# jarvis-2_0.net
KiCad netlist of a schematic drawn in EAGLE
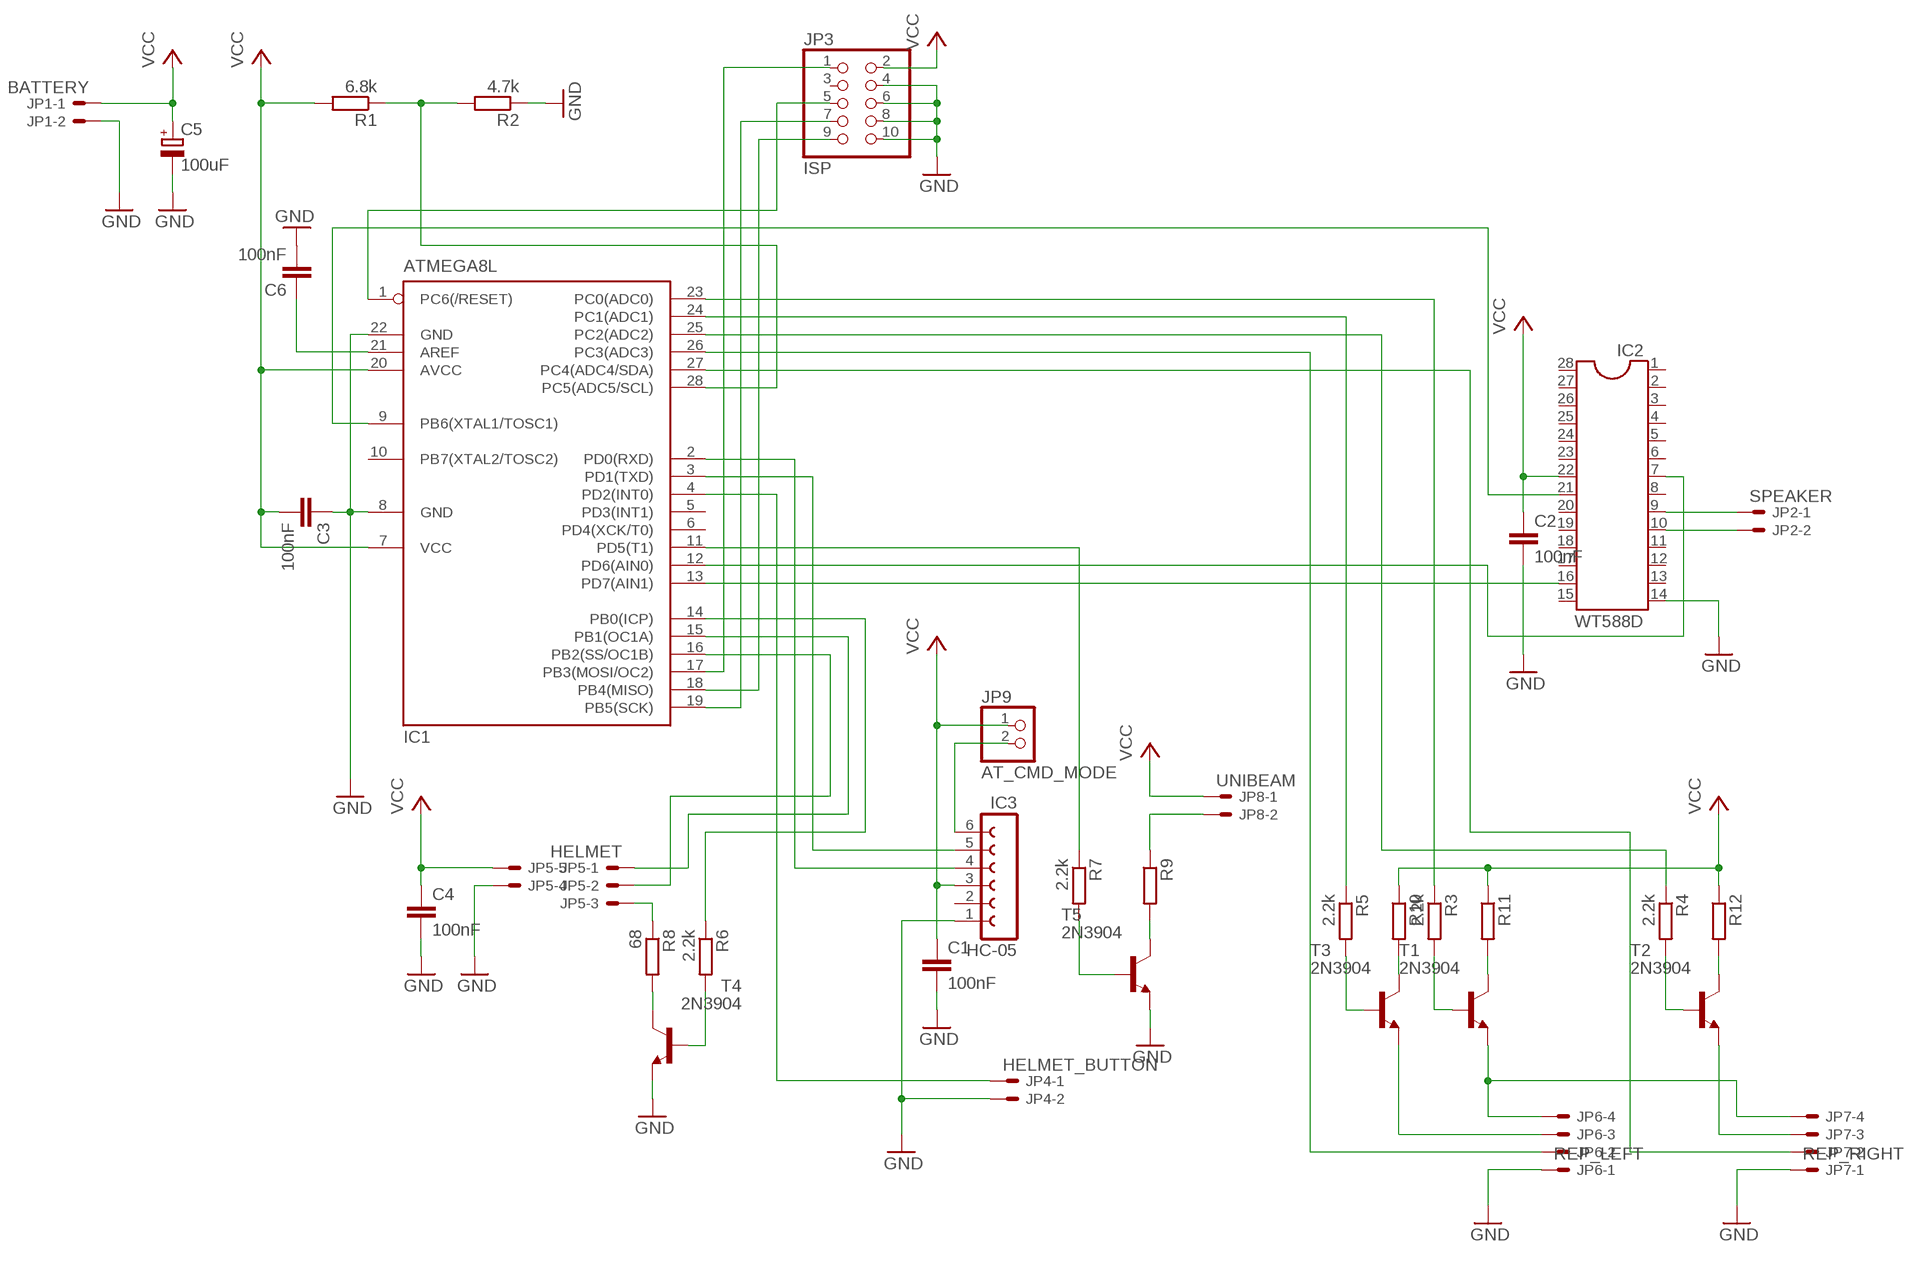
[diagram p0: schematic, sheet 1]

(export (version "E")
  (design (tool "Eeschema 10.0.6"))
  (components
    (comp (ref "C1")
      (value "100nF")
      (footprint "eagle-import:C2.5-2")
      (libsource (lib "eagle-import") (part "C2.5/2"))
    )
    (comp (ref "C2")
      (value "100nF")
      (footprint "eagle-import:C2.5-2")
      (libsource (lib "eagle-import") (part "C2.5/2"))
    )
    (comp (ref "C3")
      (value "100nF")
      (footprint "eagle-import:C2.5-2")
      (libsource (lib "eagle-import") (part "C2.5/2"))
    )
    (comp (ref "C4")
      (value "100nF")
      (footprint "eagle-import:C2.5-2")
      (libsource (lib "eagle-import") (part "C2.5/2"))
    )
    (comp (ref "C5")
      (value "100uF")
      (footprint "eagle-import:E5-5")
      (libsource (lib "eagle-import") (part "CPOL-EUE5-5"))
    )
    (comp (ref "C6")
      (value "100nF")
      (footprint "eagle-import:C2.5-2")
      (libsource (lib "eagle-import") (part "C2.5/2"))
    )
    (comp (ref "IC1")
      (value "ATMEGA8L")
      (footprint "eagle-import:DIL28-3")
      (libsource (lib "eagle-import") (part "MEGA8-P"))
    )
    (comp (ref "IC2")
      (value "WT588D")
      (footprint "eagle-import:DIL28-6")
      (libsource (lib "eagle-import") (part "DIL28"))
    )
    (comp (ref "IC3")
      (value "HC-05")
      (footprint "eagle-import:FE06")
      (libsource (lib "eagle-import") (part "FE06-1"))
    )
    (comp (ref "JP1")
      (value "BATTERY")
      (footprint "eagle-import:22-23-2021")
      (fields (field (name "MF") "MOLEX") (field (name "MPN") "22-23-2021"))
      (libsource (lib "eagle-import") (part "22-23-2021"))
    )
    (comp (ref "JP2")
      (value "SPEAKER")
      (footprint "eagle-import:22-23-2021")
      (fields (field (name "MF") "MOLEX") (field (name "MPN") "22-23-2021"))
      (libsource (lib "eagle-import") (part "22-23-2021"))
    )
    (comp (ref "JP3")
      (value "ISP")
      (footprint "eagle-import:2X05")
      (libsource (lib "eagle-import") (part "PINHD-2X5"))
    )
    (comp (ref "JP4")
      (value "HELMET_BUTTON")
      (footprint "eagle-import:22-23-2021")
      (fields (field (name "MF") "MOLEX") (field (name "MPN") "22-23-2021"))
      (libsource (lib "eagle-import") (part "22-23-2021"))
    )
    (comp (ref "JP5")
      (value "HELMET")
      (footprint "eagle-import:22-23-2051")
      (fields (field (name "MF") "MOLEX") (field (name "MPN") "22-23-2051"))
      (libsource (lib "eagle-import") (part "22-23-2051"))
    )
    (comp (ref "JP6")
      (value "REP_LEFT")
      (footprint "eagle-import:22-23-2041")
      (fields (field (name "MF") "MOLEX") (field (name "MPN") "22-23-2041"))
      (libsource (lib "eagle-import") (part "22-23-2041"))
    )
    (comp (ref "JP7")
      (value "REP_RIGHT")
      (footprint "eagle-import:22-23-2041")
      (fields (field (name "MF") "MOLEX") (field (name "MPN") "22-23-2041"))
      (libsource (lib "eagle-import") (part "22-23-2041"))
    )
    (comp (ref "JP8")
      (value "UNIBEAM")
      (footprint "eagle-import:22-23-2021")
      (fields (field (name "MF") "MOLEX") (field (name "MPN") "22-23-2021"))
      (libsource (lib "eagle-import") (part "22-23-2021"))
    )
    (comp (ref "JP9")
      (value "AT_CMD_MODE")
      (footprint "eagle-import:1X02")
      (libsource (lib "eagle-import") (part "PINHD-1X2"))
    )
    (comp (ref "R1")
      (value "6.8k")
      (footprint "eagle-import:0204_7")
      (libsource (lib "eagle-import") (part "R-EU_0204/7"))
    )
    (comp (ref "R2")
      (value "4.7k")
      (footprint "eagle-import:0204_7")
      (libsource (lib "eagle-import") (part "R-EU_0204/7"))
    )
    (comp (ref "R3")
      (value "2.2k")
      (footprint "eagle-import:0204_7")
      (libsource (lib "eagle-import") (part "R-EU_0204/7"))
    )
    (comp (ref "R4")
      (value "2.2k")
      (footprint "eagle-import:0204_7")
      (libsource (lib "eagle-import") (part "R-EU_0204/7"))
    )
    (comp (ref "R5")
      (value "2.2k")
      (footprint "eagle-import:0204_7")
      (libsource (lib "eagle-import") (part "R-EU_0204/7"))
    )
    (comp (ref "R6")
      (value "2.2k")
      (footprint "eagle-import:0204_7")
      (libsource (lib "eagle-import") (part "R-EU_0204/7"))
    )
    (comp (ref "R7")
      (value "2.2k")
      (footprint "eagle-import:0204_7")
      (libsource (lib "eagle-import") (part "R-EU_0204/7"))
    )
    (comp (ref "R8")
      (value "68")
      (footprint "eagle-import:0204_7")
      (libsource (lib "eagle-import") (part "R-EU_0204/7"))
    )
    (comp (ref "R9")
      (value "R-EU_0204/7")
      (footprint "eagle-import:0204_7")
      (libsource (lib "eagle-import") (part "R-EU_0204/7"))
    )
    (comp (ref "R10")
      (value "R-EU_0204/7")
      (footprint "eagle-import:0204_7")
      (libsource (lib "eagle-import") (part "R-EU_0204/7"))
    )
    (comp (ref "R11")
      (value "R-EU_0204/7")
      (footprint "eagle-import:0204_7")
      (libsource (lib "eagle-import") (part "R-EU_0204/7"))
    )
    (comp (ref "R12")
      (value "R-EU_0204/7")
      (footprint "eagle-import:0204_7")
      (libsource (lib "eagle-import") (part "R-EU_0204/7"))
    )
    (comp (ref "T1")
      (value "2N3904")
      (footprint "eagle-import:TO92-CBE")
      (libsource (lib "eagle-import") (part "-NPN-TO92-CBEBC546"))
    )
    (comp (ref "T2")
      (value "2N3904")
      (footprint "eagle-import:TO92-CBE")
      (libsource (lib "eagle-import") (part "-NPN-TO92-CBEBC546"))
    )
    (comp (ref "T3")
      (value "2N3904")
      (footprint "eagle-import:TO92-CBE")
      (libsource (lib "eagle-import") (part "-NPN-TO92-CBEBC546"))
    )
    (comp (ref "T4")
      (value "2N3904")
      (footprint "eagle-import:TO92-CBE")
      (libsource (lib "eagle-import") (part "-NPN-TO92-CBEBC546"))
    )
    (comp (ref "T5")
      (value "2N3904")
      (footprint "eagle-import:TO92-CBE")
      (libsource (lib "eagle-import") (part "-NPN-TO92-CBEBC546"))
    )
  )
  (nets
    (net (code "1") (name "GND") (class "Default")
      (node (ref "C1") (pin "2") (pinfunction "2_2") (pintype "passive"))
      (node (ref "C2") (pin "2") (pinfunction "2_2") (pintype "passive"))
      (node (ref "C3") (pin "1") (pinfunction "1_1") (pintype "passive"))
      (node (ref "C4") (pin "2") (pinfunction "2_2") (pintype "passive"))
      (node (ref "C5") (pin "-") (pinfunction "-_-") (pintype "passive"))
      (node (ref "C6") (pin "2") (pinfunction "2_2") (pintype "passive"))
      (node (ref "IC1") (pin "22") (pinfunction "GND_22") (pintype "power_in"))
      (node (ref "IC1") (pin "8") (pinfunction "GND_8") (pintype "power_in"))
      (node (ref "IC2") (pin "14") (pinfunction "14_14") (pintype "passive"))
      (node (ref "IC3") (pin "1") (pinfunction "1_1") (pintype "passive"))
      (node (ref "JP1") (pin "2") (pinfunction "S_2") (pintype "passive"))
      (node (ref "JP3") (pin "10") (pinfunction "10_10") (pintype "passive"))
      (node (ref "JP3") (pin "4") (pinfunction "4_4") (pintype "passive"))
      (node (ref "JP3") (pin "6") (pinfunction "6_6") (pintype "passive"))
      (node (ref "JP3") (pin "8") (pinfunction "8_8") (pintype "passive"))
      (node (ref "JP4") (pin "2") (pinfunction "S_2") (pintype "passive"))
      (node (ref "JP5") (pin "4") (pinfunction "S_4") (pintype "passive"))
      (node (ref "JP6") (pin "1") (pinfunction "S_1") (pintype "passive"))
      (node (ref "JP7") (pin "1") (pinfunction "S_1") (pintype "passive"))
      (node (ref "R2") (pin "1") (pinfunction "1_1") (pintype "passive"))
      (node (ref "T4") (pin "E") (pinfunction "E_E") (pintype "passive"))
      (node (ref "T5") (pin "E") (pinfunction "E_E") (pintype "passive"))
    )
    (net (code "2") (name "Net-(IC1-AREF)") (class "Default")
      (node (ref "C6") (pin "1") (pinfunction "1_1") (pintype "passive"))
      (node (ref "IC1") (pin "21") (pinfunction "AREF_21") (pintype "passive"))
    )
    (net (code "3") (name "Net-(IC1-PB0(ICP))") (class "Default")
      (node (ref "IC1") (pin "14") (pinfunction "PB0(ICP)_14") (pintype "bidirectional"))
      (node (ref "R6") (pin "1") (pinfunction "1_1") (pintype "passive"))
    )
    (net (code "4") (name "Net-(IC1-PB1(OC1A))") (class "Default")
      (node (ref "IC1") (pin "15") (pinfunction "PB1(OC1A)_15") (pintype "bidirectional"))
      (node (ref "JP5") (pin "1") (pinfunction "S_1") (pintype "passive"))
    )
    (net (code "5") (name "Net-(IC1-PB2(SS{slash}OC1B))") (class "Default")
      (node (ref "IC1") (pin "16") (pinfunction "PB2(SS/OC1B)_16") (pintype "bidirectional"))
      (node (ref "JP5") (pin "2") (pinfunction "S_2") (pintype "passive"))
    )
    (net (code "6") (name "Net-(IC1-PB3(MOSI{slash}OC2))") (class "Default")
      (node (ref "IC1") (pin "17") (pinfunction "PB3(MOSI/OC2)_17") (pintype "bidirectional"))
      (node (ref "JP3") (pin "1") (pinfunction "1_1") (pintype "passive"))
    )
    (net (code "7") (name "Net-(IC1-PB4(MISO))") (class "Default")
      (node (ref "IC1") (pin "18") (pinfunction "PB4(MISO)_18") (pintype "bidirectional"))
      (node (ref "JP3") (pin "9") (pinfunction "9_9") (pintype "passive"))
    )
    (net (code "8") (name "Net-(IC1-PB5(SCK))") (class "Default")
      (node (ref "IC1") (pin "19") (pinfunction "PB5(SCK)_19") (pintype "bidirectional"))
      (node (ref "JP3") (pin "7") (pinfunction "7_7") (pintype "passive"))
    )
    (net (code "9") (name "Net-(IC1-PB6(XTAL1{slash}TOSC1))") (class "Default")
      (node (ref "IC1") (pin "9") (pinfunction "PB6(XTAL1/TOSC1)_9") (pintype "bidirectional"))
      (node (ref "IC2") (pin "21") (pinfunction "21_21") (pintype "passive"))
    )
    (net (code "10") (name "Net-(IC1-PC0(ADC0))") (class "Default")
      (node (ref "IC1") (pin "23") (pinfunction "PC0(ADC0)_23") (pintype "bidirectional"))
      (node (ref "R3") (pin "1") (pinfunction "1_1") (pintype "passive"))
    )
    (net (code "11") (name "Net-(IC1-PC1(ADC1))") (class "Default")
      (node (ref "IC1") (pin "24") (pinfunction "PC1(ADC1)_24") (pintype "bidirectional"))
      (node (ref "R5") (pin "1") (pinfunction "1_1") (pintype "passive"))
    )
    (net (code "12") (name "Net-(IC1-PC2(ADC2))") (class "Default")
      (node (ref "IC1") (pin "25") (pinfunction "PC2(ADC2)_25") (pintype "bidirectional"))
      (node (ref "R4") (pin "1") (pinfunction "1_1") (pintype "passive"))
    )
    (net (code "13") (name "Net-(IC1-PC3(ADC3))") (class "Default")
      (node (ref "IC1") (pin "26") (pinfunction "PC3(ADC3)_26") (pintype "bidirectional"))
      (node (ref "JP6") (pin "2") (pinfunction "S_2") (pintype "passive"))
    )
    (net (code "14") (name "Net-(IC1-PC4(ADC4{slash}SDA))") (class "Default")
      (node (ref "IC1") (pin "27") (pinfunction "PC4(ADC4/SDA)_27") (pintype "bidirectional"))
      (node (ref "JP7") (pin "2") (pinfunction "S_2") (pintype "passive"))
    )
    (net (code "15") (name "Net-(IC1-PC5(ADC5{slash}SCL))") (class "Default")
      (node (ref "IC1") (pin "28") (pinfunction "PC5(ADC5/SCL)_28") (pintype "bidirectional"))
      (node (ref "R1") (pin "1") (pinfunction "1_1") (pintype "passive"))
      (node (ref "R2") (pin "2") (pinfunction "2_2") (pintype "passive"))
    )
    (net (code "16") (name "Net-(IC1-PC6({slash}RESET))") (class "Default")
      (node (ref "IC1") (pin "1") (pinfunction "PC6(/RESET)_1") (pintype "bidirectional"))
      (node (ref "JP3") (pin "5") (pinfunction "5_5") (pintype "passive"))
    )
    (net (code "17") (name "Net-(IC1-PD0(RXD))") (class "Default")
      (node (ref "IC1") (pin "2") (pinfunction "PD0(RXD)_2") (pintype "bidirectional"))
      (node (ref "IC3") (pin "4") (pinfunction "4_4") (pintype "passive"))
    )
    (net (code "18") (name "Net-(IC1-PD1(TXD))") (class "Default")
      (node (ref "IC1") (pin "3") (pinfunction "PD1(TXD)_3") (pintype "bidirectional"))
      (node (ref "IC3") (pin "5") (pinfunction "5_5") (pintype "passive"))
    )
    (net (code "19") (name "Net-(IC1-PD2(INT0))") (class "Default")
      (node (ref "IC1") (pin "4") (pinfunction "PD2(INT0)_4") (pintype "bidirectional"))
      (node (ref "JP4") (pin "1") (pinfunction "S_1") (pintype "passive"))
    )
    (net (code "20") (name "Net-(IC1-PD5(T1))") (class "Default")
      (node (ref "IC1") (pin "11") (pinfunction "PD5(T1)_11") (pintype "bidirectional"))
      (node (ref "R7") (pin "1") (pinfunction "1_1") (pintype "passive"))
    )
    (net (code "21") (name "Net-(IC1-PD6(AIN0))") (class "Default")
      (node (ref "IC1") (pin "12") (pinfunction "PD6(AIN0)_12") (pintype "bidirectional"))
      (node (ref "IC2") (pin "7") (pinfunction "7_7") (pintype "passive"))
    )
    (net (code "22") (name "Net-(IC1-PD7(AIN1))") (class "Default")
      (node (ref "IC1") (pin "13") (pinfunction "PD7(AIN1)_13") (pintype "bidirectional"))
      (node (ref "IC2") (pin "16") (pinfunction "16_16") (pintype "passive"))
    )
    (net (code "23") (name "Net-(IC3-Pad6)") (class "Default")
      (node (ref "IC3") (pin "6") (pinfunction "6_6") (pintype "passive"))
      (node (ref "JP9") (pin "2") (pinfunction "2_2") (pintype "passive"))
    )
    (net (code "24") (name "Net-(JP2A-S)") (class "Default")
      (node (ref "IC2") (pin "9") (pinfunction "9_9") (pintype "passive"))
      (node (ref "JP2") (pin "1") (pinfunction "S_1") (pintype "passive"))
    )
    (net (code "25") (name "Net-(JP2B-S)") (class "Default")
      (node (ref "IC2") (pin "10") (pinfunction "10_10") (pintype "passive"))
      (node (ref "JP2") (pin "2") (pinfunction "S_2") (pintype "passive"))
    )
    (net (code "26") (name "Net-(JP5C-S)") (class "Default")
      (node (ref "JP5") (pin "3") (pinfunction "S_3") (pintype "passive"))
      (node (ref "R8") (pin "1") (pinfunction "1_1") (pintype "passive"))
    )
    (net (code "27") (name "Net-(JP6C-S)") (class "Default")
      (node (ref "JP6") (pin "3") (pinfunction "S_3") (pintype "passive"))
      (node (ref "T3") (pin "E") (pinfunction "E_E") (pintype "passive"))
    )
    (net (code "28") (name "Net-(JP6D-S)") (class "Default")
      (node (ref "JP6") (pin "4") (pinfunction "S_4") (pintype "passive"))
      (node (ref "JP7") (pin "4") (pinfunction "S_4") (pintype "passive"))
      (node (ref "T1") (pin "E") (pinfunction "E_E") (pintype "passive"))
    )
    (net (code "29") (name "Net-(JP7C-S)") (class "Default")
      (node (ref "JP7") (pin "3") (pinfunction "S_3") (pintype "passive"))
      (node (ref "T2") (pin "E") (pinfunction "E_E") (pintype "passive"))
    )
    (net (code "30") (name "Net-(JP8B-S)") (class "Default")
      (node (ref "JP8") (pin "2") (pinfunction "S_2") (pintype "passive"))
      (node (ref "R9") (pin "1") (pinfunction "1_1") (pintype "passive"))
    )
    (net (code "31") (name "Net-(R3-Pad2)") (class "Default")
      (node (ref "R3") (pin "2") (pinfunction "2_2") (pintype "passive"))
      (node (ref "T1") (pin "B") (pinfunction "B_B") (pintype "passive"))
    )
    (net (code "32") (name "Net-(R4-Pad2)") (class "Default")
      (node (ref "R4") (pin "2") (pinfunction "2_2") (pintype "passive"))
      (node (ref "T2") (pin "B") (pinfunction "B_B") (pintype "passive"))
    )
    (net (code "33") (name "Net-(R5-Pad2)") (class "Default")
      (node (ref "R5") (pin "2") (pinfunction "2_2") (pintype "passive"))
      (node (ref "T3") (pin "B") (pinfunction "B_B") (pintype "passive"))
    )
    (net (code "34") (name "Net-(R6-Pad2)") (class "Default")
      (node (ref "R6") (pin "2") (pinfunction "2_2") (pintype "passive"))
      (node (ref "T4") (pin "B") (pinfunction "B_B") (pintype "passive"))
    )
    (net (code "35") (name "Net-(R7-Pad2)") (class "Default")
      (node (ref "R7") (pin "2") (pinfunction "2_2") (pintype "passive"))
      (node (ref "T5") (pin "B") (pinfunction "B_B") (pintype "passive"))
    )
    (net (code "36") (name "Net-(R8-Pad2)") (class "Default")
      (node (ref "R8") (pin "2") (pinfunction "2_2") (pintype "passive"))
      (node (ref "T4") (pin "C") (pinfunction "C_C") (pintype "passive"))
    )
    (net (code "37") (name "Net-(R9-Pad2)") (class "Default")
      (node (ref "R9") (pin "2") (pinfunction "2_2") (pintype "passive"))
      (node (ref "T5") (pin "C") (pinfunction "C_C") (pintype "passive"))
    )
    (net (code "38") (name "Net-(R10-Pad2)") (class "Default")
      (node (ref "R10") (pin "2") (pinfunction "2_2") (pintype "passive"))
      (node (ref "T3") (pin "C") (pinfunction "C_C") (pintype "passive"))
    )
    (net (code "39") (name "Net-(R11-Pad2)") (class "Default")
      (node (ref "R11") (pin "2") (pinfunction "2_2") (pintype "passive"))
      (node (ref "T1") (pin "C") (pinfunction "C_C") (pintype "passive"))
    )
    (net (code "40") (name "Net-(R12-Pad2)") (class "Default")
      (node (ref "R12") (pin "2") (pinfunction "2_2") (pintype "passive"))
      (node (ref "T2") (pin "C") (pinfunction "C_C") (pintype "passive"))
    )
    (net (code "41") (name "VCC") (class "Default")
      (node (ref "C1") (pin "1") (pinfunction "1_1") (pintype "passive"))
      (node (ref "C2") (pin "1") (pinfunction "1_1") (pintype "passive"))
      (node (ref "C3") (pin "2") (pinfunction "2_2") (pintype "passive"))
      (node (ref "C4") (pin "1") (pinfunction "1_1") (pintype "passive"))
      (node (ref "C5") (pin "+") (pinfunction "+_+") (pintype "passive"))
      (node (ref "IC1") (pin "20") (pinfunction "AVCC_20") (pintype "power_in"))
      (node (ref "IC1") (pin "7") (pinfunction "VCC_7") (pintype "power_in"))
      (node (ref "IC2") (pin "22") (pinfunction "22_22") (pintype "passive"))
      (node (ref "IC3") (pin "3") (pinfunction "3_3") (pintype "passive"))
      (node (ref "JP1") (pin "1") (pinfunction "S_1") (pintype "passive"))
      (node (ref "JP3") (pin "2") (pinfunction "2_2") (pintype "passive"))
      (node (ref "JP5") (pin "5") (pinfunction "S_5") (pintype "passive"))
      (node (ref "JP8") (pin "1") (pinfunction "S_1") (pintype "passive"))
      (node (ref "JP9") (pin "1") (pinfunction "1_1") (pintype "passive"))
      (node (ref "R1") (pin "2") (pinfunction "2_2") (pintype "passive"))
      (node (ref "R10") (pin "1") (pinfunction "1_1") (pintype "passive"))
      (node (ref "R11") (pin "1") (pinfunction "1_1") (pintype "passive"))
      (node (ref "R12") (pin "1") (pinfunction "1_1") (pintype "passive"))
    )
    (net (code "42") (name "unconnected-(IC1-PB7(XTAL2{slash}TOSC2)-Pad10)") (class "Default")
      (node (ref "IC1") (pin "10") (pinfunction "PB7(XTAL2/TOSC2)_10") (pintype "bidirectional"))
    )
    (net (code "43") (name "unconnected-(IC1-PD3(INT1)-Pad5)") (class "Default")
      (node (ref "IC1") (pin "5") (pinfunction "PD3(INT1)_5") (pintype "bidirectional"))
    )
    (net (code "44") (name "unconnected-(IC1-PD4(XCK{slash}T0)-Pad6)") (class "Default")
      (node (ref "IC1") (pin "6") (pinfunction "PD4(XCK/T0)_6") (pintype "bidirectional"))
    )
    (net (code "45") (name "unconnected-(IC2-Pad1)") (class "Default")
      (node (ref "IC2") (pin "1") (pinfunction "1_1") (pintype "passive"))
    )
    (net (code "46") (name "unconnected-(IC2-Pad2)") (class "Default")
      (node (ref "IC2") (pin "2") (pinfunction "2_2") (pintype "passive"))
    )
    (net (code "47") (name "unconnected-(IC2-Pad3)") (class "Default")
      (node (ref "IC2") (pin "3") (pinfunction "3_3") (pintype "passive"))
    )
    (net (code "48") (name "unconnected-(IC2-Pad4)") (class "Default")
      (node (ref "IC2") (pin "4") (pinfunction "4_4") (pintype "passive"))
    )
    (net (code "49") (name "unconnected-(IC2-Pad5)") (class "Default")
      (node (ref "IC2") (pin "5") (pinfunction "5_5") (pintype "passive"))
    )
    (net (code "50") (name "unconnected-(IC2-Pad6)") (class "Default")
      (node (ref "IC2") (pin "6") (pinfunction "6_6") (pintype "passive"))
    )
    (net (code "51") (name "unconnected-(IC2-Pad8)") (class "Default")
      (node (ref "IC2") (pin "8") (pinfunction "8_8") (pintype "passive"))
    )
    (net (code "52") (name "unconnected-(IC2-Pad11)") (class "Default")
      (node (ref "IC2") (pin "11") (pinfunction "11_11") (pintype "passive"))
    )
    (net (code "53") (name "unconnected-(IC2-Pad12)") (class "Default")
      (node (ref "IC2") (pin "12") (pinfunction "12_12") (pintype "passive"))
    )
    (net (code "54") (name "unconnected-(IC2-Pad13)") (class "Default")
      (node (ref "IC2") (pin "13") (pinfunction "13_13") (pintype "passive"))
    )
    (net (code "55") (name "unconnected-(IC2-Pad15)") (class "Default")
      (node (ref "IC2") (pin "15") (pinfunction "15_15") (pintype "passive"))
    )
    (net (code "56") (name "unconnected-(IC2-Pad17)") (class "Default")
      (node (ref "IC2") (pin "17") (pinfunction "17_17") (pintype "passive"))
    )
    (net (code "57") (name "unconnected-(IC2-Pad18)") (class "Default")
      (node (ref "IC2") (pin "18") (pinfunction "18_18") (pintype "passive"))
    )
    (net (code "58") (name "unconnected-(IC2-Pad19)") (class "Default")
      (node (ref "IC2") (pin "19") (pinfunction "19_19") (pintype "passive"))
    )
    (net (code "59") (name "unconnected-(IC2-Pad20)") (class "Default")
      (node (ref "IC2") (pin "20") (pinfunction "20_20") (pintype "passive"))
    )
    (net (code "60") (name "unconnected-(IC2-Pad23)") (class "Default")
      (node (ref "IC2") (pin "23") (pinfunction "23_23") (pintype "passive"))
    )
    (net (code "61") (name "unconnected-(IC2-Pad24)") (class "Default")
      (node (ref "IC2") (pin "24") (pinfunction "24_24") (pintype "passive"))
    )
    (net (code "62") (name "unconnected-(IC2-Pad25)") (class "Default")
      (node (ref "IC2") (pin "25") (pinfunction "25_25") (pintype "passive"))
    )
    (net (code "63") (name "unconnected-(IC2-Pad26)") (class "Default")
      (node (ref "IC2") (pin "26") (pinfunction "26_26") (pintype "passive"))
    )
    (net (code "64") (name "unconnected-(IC2-Pad27)") (class "Default")
      (node (ref "IC2") (pin "27") (pinfunction "27_27") (pintype "passive"))
    )
    (net (code "65") (name "unconnected-(IC2-Pad28)") (class "Default")
      (node (ref "IC2") (pin "28") (pinfunction "28_28") (pintype "passive"))
    )
    (net (code "66") (name "unconnected-(IC3-Pad2)") (class "Default")
      (node (ref "IC3") (pin "2") (pinfunction "2_2") (pintype "passive"))
    )
    (net (code "67") (name "unconnected-(JP3-Pad3)") (class "Default")
      (node (ref "JP3") (pin "3") (pinfunction "3_3") (pintype "passive"))
    )
  )
)
